# RecevieModels.net
KiCad netlist of a schematic drawn in Altium Designer
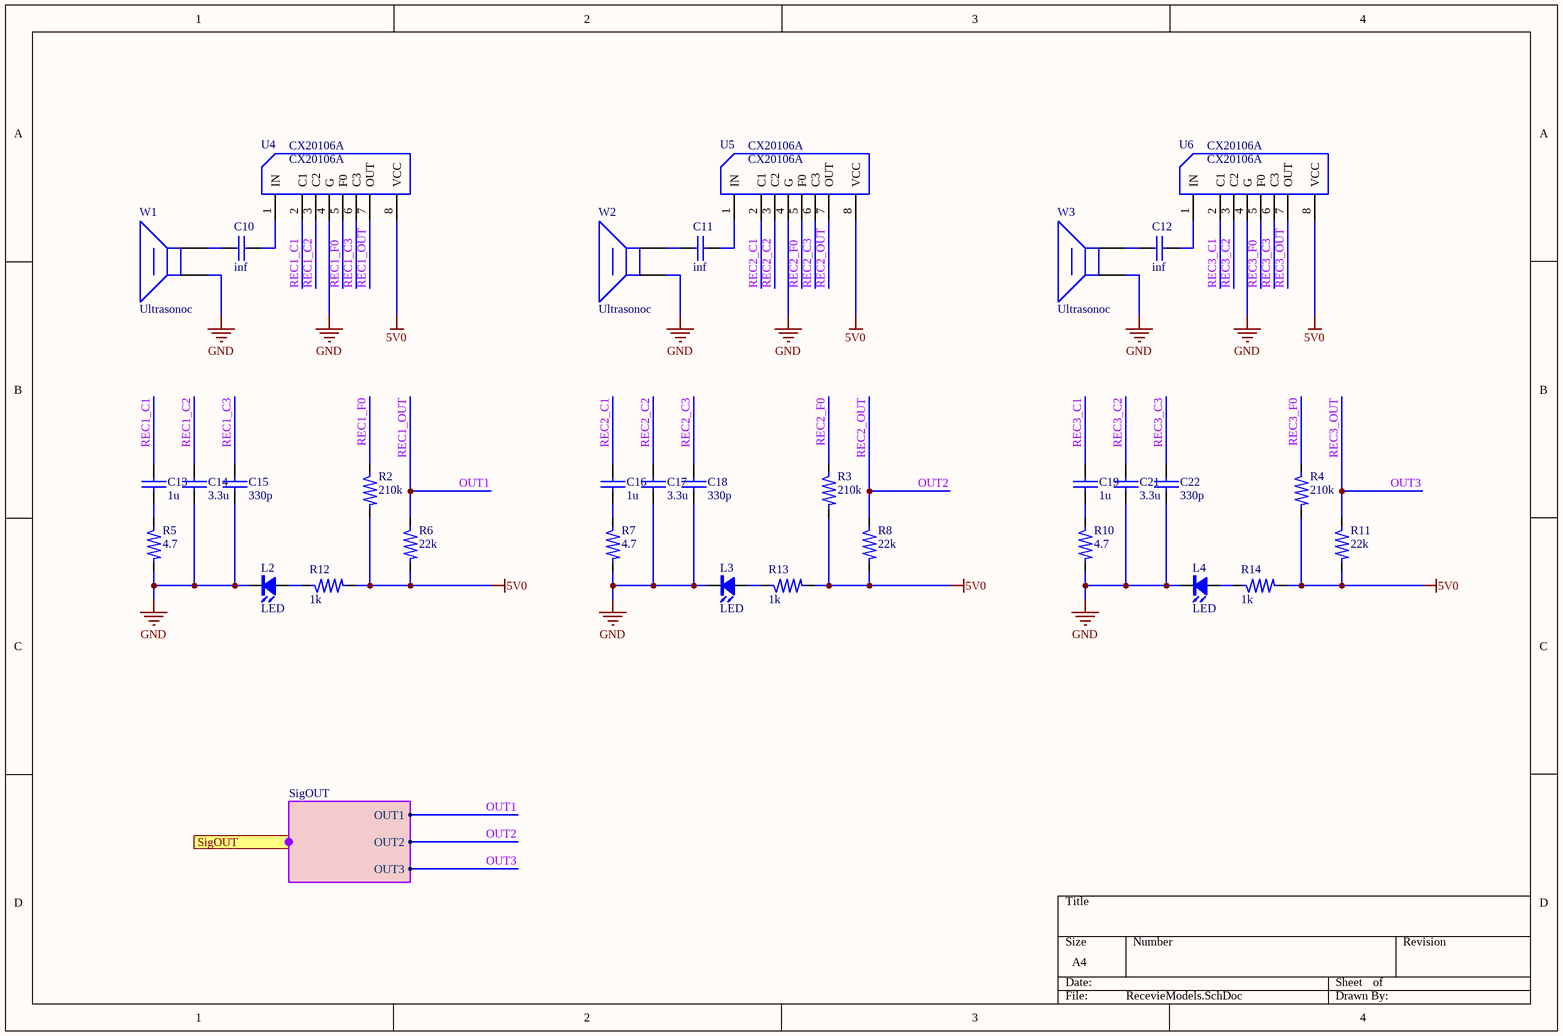
[diagram p0: RecevieModels.SchDoc]

(export (version "E")
  (design (tool "Eeschema 10.0.6"))
  (components
    (comp (ref "C10")
      (value "inf")
      (footprint "C0603")
      (description "电容")
      (libsource (lib "LQ_Integrated_Library") (part "Capacitor"))
    )
    (comp (ref "C11")
      (value "inf")
      (footprint "C0603")
      (description "电容")
      (libsource (lib "LQ_Integrated_Library") (part "Capacitor"))
    )
    (comp (ref "C12")
      (value "inf")
      (footprint "C0603")
      (description "电容")
      (libsource (lib "LQ_Integrated_Library") (part "Capacitor"))
    )
    (comp (ref "C13")
      (value "1u")
      (footprint "C0603")
      (description "电容")
      (libsource (lib "LQ_Integrated_Library") (part "Capacitor"))
    )
    (comp (ref "C14")
      (value "3.3u")
      (footprint "C0603")
      (description "电容")
      (libsource (lib "LQ_Integrated_Library") (part "Capacitor"))
    )
    (comp (ref "C15")
      (value "330p")
      (footprint "C0603")
      (description "电容")
      (libsource (lib "LQ_Integrated_Library") (part "Capacitor"))
    )
    (comp (ref "C16")
      (value "1u")
      (footprint "C0603")
      (description "电容")
      (libsource (lib "LQ_Integrated_Library") (part "Capacitor"))
    )
    (comp (ref "C17")
      (value "3.3u")
      (footprint "C0603")
      (description "电容")
      (libsource (lib "LQ_Integrated_Library") (part "Capacitor"))
    )
    (comp (ref "C18")
      (value "330p")
      (footprint "C0603")
      (description "电容")
      (libsource (lib "LQ_Integrated_Library") (part "Capacitor"))
    )
    (comp (ref "C19")
      (value "1u")
      (footprint "C0603")
      (description "电容")
      (libsource (lib "LQ_Integrated_Library") (part "Capacitor"))
    )
    (comp (ref "C21")
      (value "3.3u")
      (footprint "C0603")
      (description "电容")
      (libsource (lib "LQ_Integrated_Library") (part "Capacitor"))
    )
    (comp (ref "C22")
      (value "330p")
      (footprint "C0603")
      (description "电容")
      (libsource (lib "LQ_Integrated_Library") (part "Capacitor"))
    )
    (comp (ref "L2")
      (value "LED")
      (footprint "LED0805TB")
      (libsource (lib "LQ_Integrated_Library") (part "LED"))
    )
    (comp (ref "L3")
      (value "LED")
      (footprint "LED0805TB")
      (libsource (lib "LQ_Integrated_Library") (part "LED"))
    )
    (comp (ref "L4")
      (value "LED")
      (footprint "LED0805TB")
      (libsource (lib "LQ_Integrated_Library") (part "LED"))
    )
    (comp (ref "R2")
      (value "210k")
      (footprint "R0603")
      (description "电阻")
      (libsource (lib "LQ_Integrated_Library") (part "Resistor"))
    )
    (comp (ref "R3")
      (value "210k")
      (footprint "R0603")
      (description "电阻")
      (libsource (lib "LQ_Integrated_Library") (part "Resistor"))
    )
    (comp (ref "R4")
      (value "210k")
      (footprint "R0603")
      (description "电阻")
      (libsource (lib "LQ_Integrated_Library") (part "Resistor"))
    )
    (comp (ref "R5")
      (value "4.7")
      (footprint "R0603")
      (description "电阻")
      (libsource (lib "LQ_Integrated_Library") (part "Resistor"))
    )
    (comp (ref "R6")
      (value "22k")
      (footprint "R0603")
      (description "电阻")
      (libsource (lib "LQ_Integrated_Library") (part "Resistor"))
    )
    (comp (ref "R7")
      (value "4.7")
      (footprint "R0603")
      (description "电阻")
      (libsource (lib "LQ_Integrated_Library") (part "Resistor"))
    )
    (comp (ref "R8")
      (value "22k")
      (footprint "R0603")
      (description "电阻")
      (libsource (lib "LQ_Integrated_Library") (part "Resistor"))
    )
    (comp (ref "R10")
      (value "4.7")
      (footprint "R0603")
      (description "电阻")
      (libsource (lib "LQ_Integrated_Library") (part "Resistor"))
    )
    (comp (ref "R11")
      (value "22k")
      (footprint "R0603")
      (description "电阻")
      (libsource (lib "LQ_Integrated_Library") (part "Resistor"))
    )
    (comp (ref "R12")
      (value "1k")
      (footprint "R0603")
      (description "电阻")
      (libsource (lib "LQ_Integrated_Library") (part "Resistor"))
    )
    (comp (ref "R13")
      (value "1k")
      (footprint "R0603")
      (description "电阻")
      (libsource (lib "LQ_Integrated_Library") (part "Resistor"))
    )
    (comp (ref "R14")
      (value "1k")
      (footprint "R0603")
      (description "电阻")
      (libsource (lib "LQ_Integrated_Library") (part "Resistor"))
    )
    (comp (ref "U4")
      (value "CX20106A")
      (footprint "8Pin_100mil")
      (libsource (lib "SpaceLocator") (part "CX20106A"))
    )
    (comp (ref "U5")
      (value "CX20106A")
      (footprint "8Pin_100mil")
      (libsource (lib "SpaceLocator") (part "CX20106A"))
    )
    (comp (ref "U6")
      (value "CX20106A")
      (footprint "8Pin_100mil")
      (libsource (lib "SpaceLocator") (part "CX20106A"))
    )
    (comp (ref "W1")
      (value "Ultrasonoc")
      (footprint "Circle_1cm")
      (libsource (lib "SpaceLocator") (part "Ultrasonic"))
    )
    (comp (ref "W2")
      (value "Ultrasonoc")
      (footprint "Circle_1cm")
      (libsource (lib "SpaceLocator") (part "Ultrasonic"))
    )
    (comp (ref "W3")
      (value "Ultrasonoc")
      (footprint "Circle_1cm")
      (libsource (lib "SpaceLocator") (part "Ultrasonic"))
    )
  )
  (nets
    (net (code "2") (name "/OUT1") (class "Default")
      (node (ref "R6") (pin "2") (pinfunction "2_2") (pintype "passive"))
      (node (ref "U4") (pin "7") (pinfunction "OUT_7") (pintype "passive"))
    )
    (net (code "3") (name "/OUT2") (class "Default")
      (node (ref "R8") (pin "2") (pinfunction "2_2") (pintype "passive"))
      (node (ref "U5") (pin "7") (pinfunction "OUT_7") (pintype "passive"))
    )
    (net (code "4") (name "/OUT3") (class "Default")
      (node (ref "R11") (pin "2") (pinfunction "2_2") (pintype "passive"))
      (node (ref "U6") (pin "7") (pinfunction "OUT_7") (pintype "passive"))
    )
    (net (code "5") (name "/REC1_C1") (class "Default")
      (node (ref "C13") (pin "1") (pinfunction "1_1") (pintype "passive"))
      (node (ref "U4") (pin "2") (pinfunction "C1_2") (pintype "passive"))
    )
    (net (code "6") (name "/REC1_C2") (class "Default")
      (node (ref "C14") (pin "1") (pinfunction "1_1") (pintype "passive"))
      (node (ref "U4") (pin "3") (pinfunction "C2_3") (pintype "passive"))
    )
    (net (code "7") (name "/REC1_C3") (class "Default")
      (node (ref "C15") (pin "1") (pinfunction "1_1") (pintype "passive"))
      (node (ref "U4") (pin "6") (pinfunction "C3_6") (pintype "passive"))
    )
    (net (code "8") (name "/REC1_F0") (class "Default")
      (node (ref "R2") (pin "2") (pinfunction "2_2") (pintype "passive"))
      (node (ref "U4") (pin "5") (pinfunction "F0_5") (pintype "passive"))
    )
    (net (code "9") (name "/REC2_C1") (class "Default")
      (node (ref "C16") (pin "1") (pinfunction "1_1") (pintype "passive"))
      (node (ref "U5") (pin "2") (pinfunction "C1_2") (pintype "passive"))
    )
    (net (code "10") (name "/REC2_C2") (class "Default")
      (node (ref "C17") (pin "1") (pinfunction "1_1") (pintype "passive"))
      (node (ref "U5") (pin "3") (pinfunction "C2_3") (pintype "passive"))
    )
    (net (code "11") (name "/REC2_C3") (class "Default")
      (node (ref "C18") (pin "1") (pinfunction "1_1") (pintype "passive"))
      (node (ref "U5") (pin "6") (pinfunction "C3_6") (pintype "passive"))
    )
    (net (code "12") (name "/REC2_F0") (class "Default")
      (node (ref "R3") (pin "2") (pinfunction "2_2") (pintype "passive"))
      (node (ref "U5") (pin "5") (pinfunction "F0_5") (pintype "passive"))
    )
    (net (code "13") (name "/REC3_C1") (class "Default")
      (node (ref "C19") (pin "1") (pinfunction "1_1") (pintype "passive"))
      (node (ref "U6") (pin "2") (pinfunction "C1_2") (pintype "passive"))
    )
    (net (code "14") (name "/REC3_C2") (class "Default")
      (node (ref "C21") (pin "1") (pinfunction "1_1") (pintype "passive"))
      (node (ref "U6") (pin "3") (pinfunction "C2_3") (pintype "passive"))
    )
    (net (code "15") (name "/REC3_C3") (class "Default")
      (node (ref "C22") (pin "1") (pinfunction "1_1") (pintype "passive"))
      (node (ref "U6") (pin "6") (pinfunction "C3_6") (pintype "passive"))
    )
    (net (code "16") (name "/REC3_F0") (class "Default")
      (node (ref "R4") (pin "2") (pinfunction "2_2") (pintype "passive"))
      (node (ref "U6") (pin "5") (pinfunction "F0_5") (pintype "passive"))
    )
    (net (code "18") (name "5V0") (class "Default")
      (node (ref "R11") (pin "1") (pinfunction "1_1") (pintype "passive"))
      (node (ref "R12") (pin "1") (pinfunction "1_1") (pintype "passive"))
      (node (ref "R13") (pin "1") (pinfunction "1_1") (pintype "passive"))
      (node (ref "R14") (pin "1") (pinfunction "1_1") (pintype "passive"))
      (node (ref "R2") (pin "1") (pinfunction "1_1") (pintype "passive"))
      (node (ref "R3") (pin "1") (pinfunction "1_1") (pintype "passive"))
      (node (ref "R4") (pin "1") (pinfunction "1_1") (pintype "passive"))
      (node (ref "R6") (pin "1") (pinfunction "1_1") (pintype "passive"))
      (node (ref "R8") (pin "1") (pinfunction "1_1") (pintype "passive"))
      (node (ref "U4") (pin "8") (pinfunction "VCC_8") (pintype "passive"))
      (node (ref "U5") (pin "8") (pinfunction "VCC_8") (pintype "passive"))
      (node (ref "U6") (pin "8") (pinfunction "VCC_8") (pintype "passive"))
    )
    (net (code "19") (name "GND") (class "Default")
      (node (ref "C14") (pin "2") (pinfunction "2_2") (pintype "passive"))
      (node (ref "C15") (pin "2") (pinfunction "2_2") (pintype "passive"))
      (node (ref "C17") (pin "2") (pinfunction "2_2") (pintype "passive"))
      (node (ref "C18") (pin "2") (pinfunction "2_2") (pintype "passive"))
      (node (ref "C21") (pin "2") (pinfunction "2_2") (pintype "passive"))
      (node (ref "C22") (pin "2") (pinfunction "2_2") (pintype "passive"))
      (node (ref "L2") (pin "2") (pinfunction "K_2") (pintype "passive"))
      (node (ref "L3") (pin "2") (pinfunction "K_2") (pintype "passive"))
      (node (ref "L4") (pin "2") (pinfunction "K_2") (pintype "passive"))
      (node (ref "R10") (pin "1") (pinfunction "1_1") (pintype "passive"))
      (node (ref "R5") (pin "1") (pinfunction "1_1") (pintype "passive"))
      (node (ref "R7") (pin "1") (pinfunction "1_1") (pintype "passive"))
      (node (ref "U4") (pin "4") (pinfunction "G_4") (pintype "passive"))
      (node (ref "U5") (pin "4") (pinfunction "G_4") (pintype "passive"))
      (node (ref "U6") (pin "4") (pinfunction "G_4") (pintype "passive"))
      (node (ref "W1") (pin "1") (pinfunction "1_1") (pintype "passive"))
      (node (ref "W2") (pin "1") (pinfunction "1_1") (pintype "passive"))
      (node (ref "W3") (pin "1") (pinfunction "1_1") (pintype "passive"))
    )
    (net (code "20") (name "Net-(C10-Pad1)") (class "Default")
      (node (ref "C10") (pin "1") (pinfunction "1_1") (pintype "passive"))
      (node (ref "W1") (pin "2") (pinfunction "2_2") (pintype "passive"))
    )
    (net (code "21") (name "Net-(C11-Pad1)") (class "Default")
      (node (ref "C11") (pin "1") (pinfunction "1_1") (pintype "passive"))
      (node (ref "W2") (pin "2") (pinfunction "2_2") (pintype "passive"))
    )
    (net (code "22") (name "Net-(C12-Pad1)") (class "Default")
      (node (ref "C12") (pin "1") (pinfunction "1_1") (pintype "passive"))
      (node (ref "W3") (pin "2") (pinfunction "2_2") (pintype "passive"))
    )
    (net (code "23") (name "Net-(C13-Pad2)") (class "Default")
      (node (ref "C13") (pin "2") (pinfunction "2_2") (pintype "passive"))
      (node (ref "R5") (pin "2") (pinfunction "2_2") (pintype "passive"))
    )
    (net (code "24") (name "Net-(C16-Pad2)") (class "Default")
      (node (ref "C16") (pin "2") (pinfunction "2_2") (pintype "passive"))
      (node (ref "R7") (pin "2") (pinfunction "2_2") (pintype "passive"))
    )
    (net (code "25") (name "Net-(C19-Pad2)") (class "Default")
      (node (ref "C19") (pin "2") (pinfunction "2_2") (pintype "passive"))
      (node (ref "R10") (pin "2") (pinfunction "2_2") (pintype "passive"))
    )
    (net (code "26") (name "Net-(L2-A)") (class "Default")
      (node (ref "L2") (pin "1") (pinfunction "A_1") (pintype "passive"))
      (node (ref "R12") (pin "2") (pinfunction "2_2") (pintype "passive"))
    )
    (net (code "27") (name "Net-(L3-A)") (class "Default")
      (node (ref "L3") (pin "1") (pinfunction "A_1") (pintype "passive"))
      (node (ref "R13") (pin "2") (pinfunction "2_2") (pintype "passive"))
    )
    (net (code "28") (name "Net-(L4-A)") (class "Default")
      (node (ref "L4") (pin "1") (pinfunction "A_1") (pintype "passive"))
      (node (ref "R14") (pin "2") (pinfunction "2_2") (pintype "passive"))
    )
    (net (code "29") (name "Net-(U4-IN)") (class "Default")
      (node (ref "C10") (pin "2") (pinfunction "2_2") (pintype "passive"))
      (node (ref "U4") (pin "1") (pinfunction "IN_1") (pintype "passive"))
    )
    (net (code "30") (name "Net-(U5-IN)") (class "Default")
      (node (ref "C11") (pin "2") (pinfunction "2_2") (pintype "passive"))
      (node (ref "U5") (pin "1") (pinfunction "IN_1") (pintype "passive"))
    )
    (net (code "31") (name "Net-(U6-IN)") (class "Default")
      (node (ref "C12") (pin "2") (pinfunction "2_2") (pintype "passive"))
      (node (ref "U6") (pin "1") (pinfunction "IN_1") (pintype "passive"))
    )
  )
)
